# SCHv2.net
KiCad netlist of a schematic drawn in EAGLE
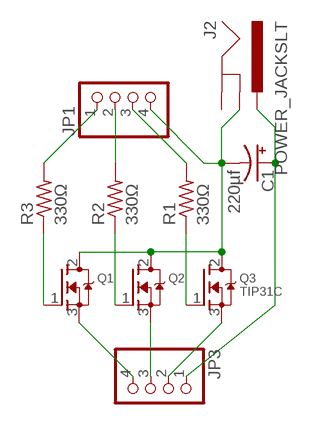
[diagram p0: schematic, sheet 1]

(export (version "E")
  (design (tool "Eeschema 10.0.6"))
  (components
    (comp (ref "C1")
      (value "220µf")
      (footprint "eagle-import:E2,5-7")
      (libsource (lib "eagle-import") (part "CPOL-USE2.5-7"))
    )
    (comp (ref "J2")
      (value "POWER_JACKSLT")
      (footprint "eagle-import:POWER_JACK_SLOT")
      (libsource (lib "eagle-import") (part "POWER_JACKSLT"))
    )
    (comp (ref "JP1")
      (value "PINHD-1X4/90")
      (footprint "eagle-import:1X04_90")
      (libsource (lib "eagle-import") (part "PINHD-1X4/90"))
    )
    (comp (ref "JP3")
      (value "PINHD-1X4/90")
      (footprint "eagle-import:1X04_90")
      (libsource (lib "eagle-import") (part "PINHD-1X4/90"))
    )
    (comp (ref "Q1")
      (value "MOSFET-NGDS_TO220V")
      (footprint "eagle-import:TO220V")
      (libsource (lib "eagle-import") (part "MOSFET-NGDS_TO220V"))
    )
    (comp (ref "Q2")
      (value "MOSFET-NGDS_TO220V")
      (footprint "eagle-import:TO220V")
      (libsource (lib "eagle-import") (part "MOSFET-NGDS_TO220V"))
    )
    (comp (ref "Q3")
      (value "TIP31C")
      (footprint "eagle-import:TO220V")
      (libsource (lib "eagle-import") (part "MOSFET-NGDS_TO220V"))
    )
    (comp (ref "R1")
      (value "330Ω")
      (footprint "eagle-import:0207_7")
      (libsource (lib "eagle-import") (part "R-US_0207/7"))
    )
    (comp (ref "R2")
      (value "330Ω")
      (footprint "eagle-import:0207_7")
      (libsource (lib "eagle-import") (part "R-US_0207/7"))
    )
    (comp (ref "R3")
      (value "330Ω")
      (footprint "eagle-import:0207_7")
      (libsource (lib "eagle-import") (part "R-US_0207/7"))
    )
  )
  (nets
    (net (code "1") (name "Net-(C1-Pad+)") (class "Default")
      (node (ref "C1") (pin "+") (pinfunction "+_+") (pintype "passive"))
      (node (ref "J2") (pin "PWR") (pinfunction "PWR_PWR") (pintype "bidirectional"))
      (node (ref "JP3") (pin "1") (pinfunction "1_1") (pintype "passive"))
    )
    (net (code "2") (name "Net-(J2-GNDBREAK)") (class "Default")
      (node (ref "C1") (pin "-") (pinfunction "-_-") (pintype "passive"))
      (node (ref "J2") (pin "GND@1") (pinfunction "GNDBREAK_GND@1") (pintype "bidirectional"))
      (node (ref "JP1") (pin "4") (pinfunction "4_4") (pintype "passive"))
      (node (ref "Q1") (pin "2") (pinfunction "D_2") (pintype "bidirectional"))
      (node (ref "Q2") (pin "2") (pinfunction "D_2") (pintype "bidirectional"))
      (node (ref "Q3") (pin "2") (pinfunction "D_2") (pintype "bidirectional"))
    )
    (net (code "3") (name "Net-(JP1-Pad1)") (class "Default")
      (node (ref "JP1") (pin "1") (pinfunction "1_1") (pintype "passive"))
      (node (ref "R3") (pin "2") (pinfunction "2_2") (pintype "passive"))
    )
    (net (code "4") (name "Net-(JP1-Pad2)") (class "Default")
      (node (ref "JP1") (pin "2") (pinfunction "2_2") (pintype "passive"))
      (node (ref "R2") (pin "2") (pinfunction "2_2") (pintype "passive"))
    )
    (net (code "5") (name "Net-(JP1-Pad3)") (class "Default")
      (node (ref "JP1") (pin "3") (pinfunction "3_3") (pintype "passive"))
      (node (ref "R1") (pin "2") (pinfunction "2_2") (pintype "passive"))
    )
    (net (code "6") (name "Net-(Q1-G)") (class "Default")
      (node (ref "Q1") (pin "1") (pinfunction "G_1") (pintype "bidirectional"))
      (node (ref "R3") (pin "1") (pinfunction "1_1") (pintype "passive"))
    )
    (net (code "7") (name "Net-(Q1-S)") (class "Default")
      (node (ref "JP3") (pin "4") (pinfunction "4_4") (pintype "passive"))
      (node (ref "Q1") (pin "3") (pinfunction "S_3") (pintype "bidirectional"))
    )
    (net (code "8") (name "Net-(Q2-G)") (class "Default")
      (node (ref "Q2") (pin "1") (pinfunction "G_1") (pintype "bidirectional"))
      (node (ref "R2") (pin "1") (pinfunction "1_1") (pintype "passive"))
    )
    (net (code "9") (name "Net-(Q2-S)") (class "Default")
      (node (ref "JP3") (pin "3") (pinfunction "3_3") (pintype "passive"))
      (node (ref "Q2") (pin "3") (pinfunction "S_3") (pintype "bidirectional"))
    )
    (net (code "10") (name "Net-(Q3-G)") (class "Default")
      (node (ref "Q3") (pin "1") (pinfunction "G_1") (pintype "bidirectional"))
      (node (ref "R1") (pin "1") (pinfunction "1_1") (pintype "passive"))
    )
    (net (code "11") (name "Net-(Q3-S)") (class "Default")
      (node (ref "JP3") (pin "2") (pinfunction "2_2") (pintype "passive"))
      (node (ref "Q3") (pin "3") (pinfunction "S_3") (pintype "bidirectional"))
    )
    (net (code "12") (name "unconnected-(J2-GND-PadGND@2)") (class "Default")
      (node (ref "J2") (pin "GND@2") (pinfunction "GND_GND@2") (pintype "bidirectional"))
    )
  )
)
